# Peltier.net
KiCad netlist of a schematic drawn in Altium Designer
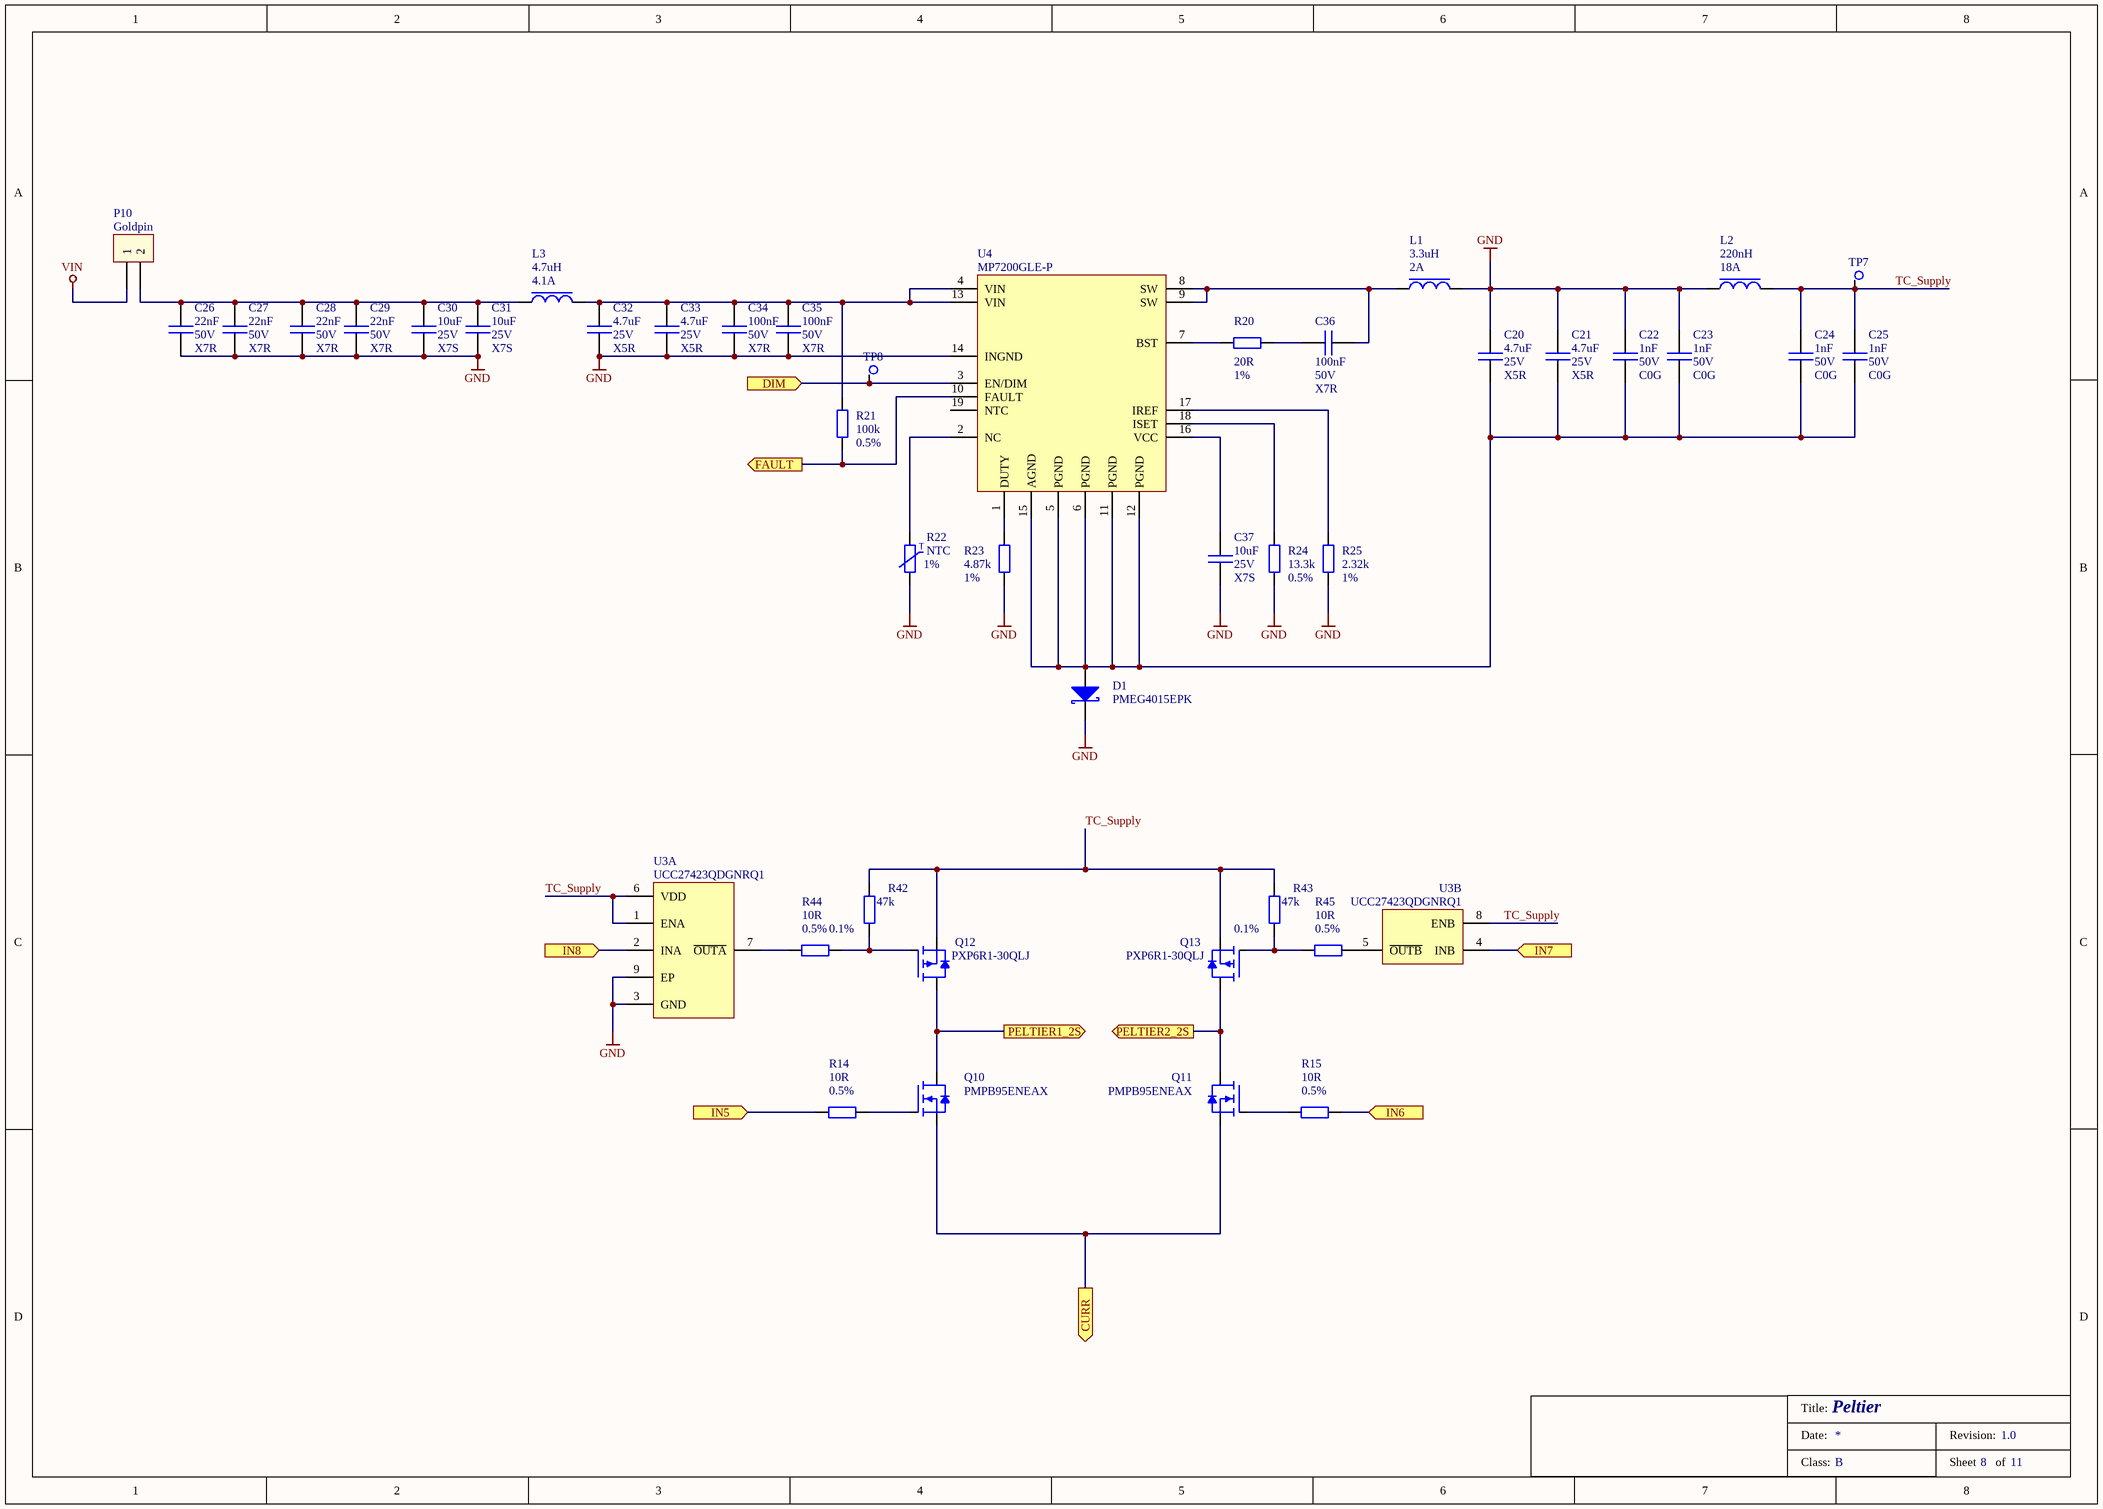
[diagram p0: Peltier.SchDoc]

(export (version "E")
  (design (tool "Eeschema 10.0.6"))
  (components
    (comp (ref "C20")
      (value "4.7uF")
      (footprint "C_0603")
      (description "Capacitor")
      (fields
        (field (name "VOLTAGE") "25V")
        (field (name "DIELECTRIC") "X5R")
        (field (name "PART NUMBER") "C_4.7uF_25V_0603")
        (field (name "MANUFACTURER") "TDK")
      )
      (libsource (lib "ProgresjaSpace") (part "C"))
    )
    (comp (ref "C21")
      (value "4.7uF")
      (footprint "C_0603")
      (description "Capacitor")
      (fields
        (field (name "VOLTAGE") "25V")
        (field (name "DIELECTRIC") "X5R")
        (field (name "PART NUMBER") "C_4.7uF_25V_0603")
        (field (name "MANUFACTURER") "TDK")
      )
      (libsource (lib "ProgresjaSpace") (part "C"))
    )
    (comp (ref "C22")
      (value "1nF")
      (footprint "C_0603")
      (description "Capacitor")
      (fields
        (field (name "VOLTAGE") "50V")
        (field (name "DIELECTRIC") "C0G")
        (field (name "PART NUMBER") "C_1nF_50V_0603")
        (field (name "MANUFACTURER") "Kemet")
      )
      (libsource (lib "ProgresjaSpace") (part "C"))
    )
    (comp (ref "C23")
      (value "1nF")
      (footprint "C_0603")
      (description "Capacitor")
      (fields
        (field (name "VOLTAGE") "50V")
        (field (name "DIELECTRIC") "C0G")
        (field (name "PART NUMBER") "C_1nF_50V_0603")
        (field (name "MANUFACTURER") "Kemet")
      )
      (libsource (lib "ProgresjaSpace") (part "C"))
    )
    (comp (ref "C24")
      (value "1nF")
      (footprint "C_0603")
      (description "Capacitor")
      (fields
        (field (name "VOLTAGE") "50V")
        (field (name "DIELECTRIC") "C0G")
        (field (name "PART NUMBER") "C_1nF_50V_0603")
        (field (name "MANUFACTURER") "Kemet")
      )
      (libsource (lib "ProgresjaSpace") (part "C"))
    )
    (comp (ref "C25")
      (value "1nF")
      (footprint "C_0603")
      (description "Capacitor")
      (fields
        (field (name "VOLTAGE") "50V")
        (field (name "DIELECTRIC") "C0G")
        (field (name "PART NUMBER") "C_1nF_50V_0603")
        (field (name "MANUFACTURER") "Kemet")
      )
      (libsource (lib "ProgresjaSpace") (part "C"))
    )
    (comp (ref "C26")
      (value "22nF")
      (footprint "C_0603")
      (description "Capacitor")
      (fields
        (field (name "VOLTAGE") "50V")
        (field (name "DIELECTRIC") "X7R")
        (field (name "PART NUMBER") "C_22nF_50V_0603")
        (field (name "MANUFACTURER") "Kemet")
      )
      (libsource (lib "ProgresjaSpace") (part "C"))
    )
    (comp (ref "C27")
      (value "22nF")
      (footprint "C_0603")
      (description "Capacitor")
      (fields
        (field (name "VOLTAGE") "50V")
        (field (name "DIELECTRIC") "X7R")
        (field (name "PART NUMBER") "C_22nF_50V_0603")
        (field (name "MANUFACTURER") "Kemet")
      )
      (libsource (lib "ProgresjaSpace") (part "C"))
    )
    (comp (ref "C28")
      (value "22nF")
      (footprint "C_0603")
      (description "Capacitor")
      (fields
        (field (name "VOLTAGE") "50V")
        (field (name "DIELECTRIC") "X7R")
        (field (name "PART NUMBER") "C_22nF_50V_0603")
        (field (name "MANUFACTURER") "Kemet")
      )
      (libsource (lib "ProgresjaSpace") (part "C"))
    )
    (comp (ref "C29")
      (value "22nF")
      (footprint "C_0603")
      (description "Capacitor")
      (fields
        (field (name "VOLTAGE") "50V")
        (field (name "DIELECTRIC") "X7R")
        (field (name "PART NUMBER") "C_22nF_50V_0603")
        (field (name "MANUFACTURER") "Kemet")
      )
      (libsource (lib "ProgresjaSpace") (part "C"))
    )
    (comp (ref "C30")
      (value "10uF")
      (footprint "C_0805")
      (description "Capacitor")
      (fields
        (field (name "VOLTAGE") "25V")
        (field (name "DIELECTRIC") "X7S")
        (field (name "PART NUMBER") "C_10uF_25V_0805")
        (field (name "MANUFACTURER") "TDK")
      )
      (libsource (lib "ProgresjaSpace") (part "C"))
    )
    (comp (ref "C31")
      (value "10uF")
      (footprint "C_0805")
      (description "Capacitor")
      (fields
        (field (name "VOLTAGE") "25V")
        (field (name "DIELECTRIC") "X7S")
        (field (name "PART NUMBER") "C_10uF_25V_0805")
        (field (name "MANUFACTURER") "TDK")
      )
      (libsource (lib "ProgresjaSpace") (part "C"))
    )
    (comp (ref "C32")
      (value "4.7uF")
      (footprint "C_0603")
      (description "Capacitor")
      (fields
        (field (name "VOLTAGE") "25V")
        (field (name "DIELECTRIC") "X5R")
        (field (name "PART NUMBER") "C_4.7uF_25V_0603")
        (field (name "MANUFACTURER") "TDK")
      )
      (libsource (lib "ProgresjaSpace") (part "C"))
    )
    (comp (ref "C33")
      (value "4.7uF")
      (footprint "C_0603")
      (description "Capacitor")
      (fields
        (field (name "VOLTAGE") "25V")
        (field (name "DIELECTRIC") "X5R")
        (field (name "PART NUMBER") "C_4.7uF_25V_0603")
        (field (name "MANUFACTURER") "TDK")
      )
      (libsource (lib "ProgresjaSpace") (part "C"))
    )
    (comp (ref "C34")
      (value "100nF")
      (footprint "C_0603")
      (description "Capacitor")
      (fields
        (field (name "VOLTAGE") "50V")
        (field (name "DIELECTRIC") "X7R")
        (field (name "PART NUMBER") "C_100nF_50V_0603")
        (field (name "MANUFACTURER") "Kemet")
      )
      (libsource (lib "ProgresjaSpace") (part "C"))
    )
    (comp (ref "C35")
      (value "100nF")
      (footprint "C_0603")
      (description "Capacitor")
      (fields
        (field (name "VOLTAGE") "50V")
        (field (name "DIELECTRIC") "X7R")
        (field (name "PART NUMBER") "C_100nF_50V_0603")
        (field (name "MANUFACTURER") "Kemet")
      )
      (libsource (lib "ProgresjaSpace") (part "C"))
    )
    (comp (ref "C36")
      (value "100nF")
      (footprint "C_0603")
      (description "Capacitor")
      (fields
        (field (name "VOLTAGE") "50V")
        (field (name "DIELECTRIC") "X7R")
        (field (name "PART NUMBER") "C_100nF_50V_0603")
        (field (name "MANUFACTURER") "Kemet")
      )
      (libsource (lib "ProgresjaSpace") (part "C"))
    )
    (comp (ref "C37")
      (value "10uF")
      (footprint "C_0805")
      (description "Capacitor")
      (fields
        (field (name "VOLTAGE") "25V")
        (field (name "DIELECTRIC") "X7S")
        (field (name "PART NUMBER") "C_10uF_25V_0805")
        (field (name "MANUFACTURER") "TDK")
      )
      (libsource (lib "ProgresjaSpace") (part "C"))
    )
    (comp (ref "D1")
      (value "PMEG4015EPK")
      (footprint "D_SOD_1608")
      (description "40 V, 1.5 A low VF MEGA Schottky barrier rectifier")
      (fields (field (name "MANUFACTURER") "Nexperia") (field (name "Comment") "D_SHOTTKY"))
      (libsource (lib "ProgresjaSpace") (part "D_SHOTTKY"))
    )
    (comp (ref "L1")
      (value "3.3uH")
      (footprint "L_1008_05")
      (description "Shielded, soft-termination")
      (fields
        (field (name "MAX CURRENT") "2A")
        (field (name "PART NUMBER") "TFM252012ALVA3R3MTAA")
        (field (name "MANUFACTURER") "TDK")
      )
      (libsource (lib "ProgresjaSpace") (part "L_Core"))
    )
    (comp (ref "L2")
      (value "220nH")
      (footprint "L_2020")
      (description "Shielded Inductors, High Temperature")
      (fields
        (field (name "MAX CURRENT") "18A")
        (field (name "PART NUMBER") "IHLP2020CZERR22M8A")
        (field (name "MANUFACTURER") "Vishay")
      )
      (libsource (lib "ProgresjaSpace") (part "L_Core"))
    )
    (comp (ref "L3")
      (value "4.7uH")
      (footprint "L_2020")
      (description "Shielded automotive Inductors, High Temperature")
      (fields
        (field (name "MAX CURRENT") "4.1A")
        (field (name "PART NUMBER") "IHLP2020CZER4R7M5A")
        (field (name "MANUFACTURER") "Vishay")
      )
      (libsource (lib "ProgresjaSpace") (part "L_Core"))
    )
    (comp (ref "P10")
      (value "P_Header_2")
      (footprint "GOLDPIN_2")
      (description "Goldpin")
      (fields
        (field (name "DESC") "Goldpin")
        (field (name "PART NUMBER") "77311-818-02LF")
        (field (name "MANUFACTURER") "AMPHENOL")
      )
      (libsource (lib "ProgresjaSpace") (part "P_Header_2"))
    )
    (comp (ref "Q10")
      (value "PMPB95ENEAX")
      (footprint "UDFN_6_3123")
      (description "Single N-channel Trench MOSFET")
      (fields (field (name "MANUFACTURER") "NEXPERIA") (field (name "Comment") "Q_NMOSFET"))
      (libsource (lib "ProgresjaSpace") (part "Q_NMOSFET"))
    )
    (comp (ref "Q11")
      (value "PMPB95ENEAX")
      (footprint "UDFN_6_3123")
      (description "Single N-channel Trench MOSFET")
      (fields (field (name "MANUFACTURER") "NEXPERIA") (field (name "Comment") "Q_NMOSFET"))
      (libsource (lib "ProgresjaSpace") (part "Q_NMOSFET"))
    )
    (comp (ref "Q12")
      (value "PXP6R1-30QLJ")
      (footprint "WDFN_8")
      (description "Low Vgs Single P-Channel")
      (fields (field (name "MANUFACTURER") "NEXPERIA") (field (name "Comment") "Q_PMOSFET"))
      (libsource (lib "ProgresjaSpace") (part "Q_PMOSFET"))
    )
    (comp (ref "Q13")
      (value "PXP6R1-30QLJ")
      (footprint "WDFN_8")
      (description "Low Vgs Single P-Channel")
      (fields (field (name "MANUFACTURER") "NEXPERIA") (field (name "Comment") "Q_PMOSFET"))
      (libsource (lib "ProgresjaSpace") (part "Q_PMOSFET"))
    )
    (comp (ref "R14")
      (value "10R")
      (footprint "R_0603")
      (fields
        (field (name "TOLERANCE") "0.5%")
        (field (name "PART NUMBER") "R_10R_75V_0603")
        (field (name "VOLTAGE") "75V")
        (field (name "MANUFACTURER") "Vishay")
      )
      (libsource (lib "ProgresjaSpace") (part "R"))
    )
    (comp (ref "R15")
      (value "10R")
      (footprint "R_0603")
      (fields
        (field (name "TOLERANCE") "0.5%")
        (field (name "PART NUMBER") "R_10R_75V_0603")
        (field (name "VOLTAGE") "75V")
        (field (name "MANUFACTURER") "Vishay")
      )
      (libsource (lib "ProgresjaSpace") (part "R"))
    )
    (comp (ref "R20")
      (value "20R")
      (footprint "R_0603")
      (fields
        (field (name "TOLERANCE") "1%")
        (field (name "PART NUMBER") "R_20R_75V_0603")
        (field (name "VOLTAGE") "75V")
        (field (name "MANUFACTURER") "Panasonic")
      )
      (libsource (lib "ProgresjaSpace") (part "R"))
    )
    (comp (ref "R21")
      (value "100k")
      (footprint "R_0402")
      (fields
        (field (name "TOLERANCE") "0.5%")
        (field (name "PART NUMBER") "R_100k_50V_0402")
        (field (name "VOLTAGE") "50V")
        (field (name "MANUFACTURER") "Vishay")
      )
      (libsource (lib "") (part "R_1"))
    )
    (comp (ref "R22")
      (value "R_B572xxV5")
      (footprint "R_0402")
      (description "NTC")
      (fields
        (field (name "DESC") "NTC")
        (field (name "TOLERANCE") "1%")
        (field (name "PART NUMBER") "B57232V5103F360")
        (field (name "MANUFACTURER") "TDK")
      )
      (libsource (lib "ProgresjaSpace") (part "R_B572xxV5"))
    )
    (comp (ref "R23")
      (value "4.87k")
      (footprint "R_0402")
      (fields
        (field (name "TOLERANCE") "1%")
        (field (name "PART NUMBER") "R_4.87k_50V_0402")
        (field (name "VOLTAGE") "50V")
        (field (name "MANUFACTURER") "Panasonic")
      )
      (libsource (lib "") (part "R_1"))
    )
    (comp (ref "R24")
      (value "13.3k")
      (footprint "R_0402")
      (fields
        (field (name "TOLERANCE") "0.5%")
        (field (name "PART NUMBER") "R_13.3k_50V_0402")
        (field (name "VOLTAGE") "50V")
        (field (name "MANUFACTURER") "Panasonic")
      )
      (libsource (lib "") (part "R_1"))
    )
    (comp (ref "R25")
      (value "2.32k")
      (footprint "R_0402")
      (fields
        (field (name "TOLERANCE") "1%")
        (field (name "PART NUMBER") "R_2.32k_50V_0402")
        (field (name "VOLTAGE") "50V")
        (field (name "MANUFACTURER") "Panasonic")
      )
      (libsource (lib "") (part "R_1"))
    )
    (comp (ref "R42")
      (value "47k")
      (footprint "R_0402")
      (fields
        (field (name "TOLERANCE") "0.1%")
        (field (name "PART NUMBER") "R_47k_50V_0402")
        (field (name "VOLTAGE") "50V")
        (field (name "MANUFACTURER") "Vishay")
      )
      (libsource (lib "") (part "R_2"))
    )
    (comp (ref "R43")
      (value "47k")
      (footprint "R_0402")
      (fields
        (field (name "TOLERANCE") "0.1%")
        (field (name "PART NUMBER") "R_47k_50V_0402")
        (field (name "VOLTAGE") "50V")
        (field (name "MANUFACTURER") "Vishay")
      )
      (libsource (lib "") (part "R_2"))
    )
    (comp (ref "R44")
      (value "10R")
      (footprint "R_0603")
      (fields
        (field (name "TOLERANCE") "0.5%")
        (field (name "PART NUMBER") "R_10R_75V_0603")
        (field (name "VOLTAGE") "75V")
        (field (name "MANUFACTURER") "Vishay")
      )
      (libsource (lib "ProgresjaSpace") (part "R"))
    )
    (comp (ref "R45")
      (value "10R")
      (footprint "R_0603")
      (fields
        (field (name "TOLERANCE") "0.5%")
        (field (name "PART NUMBER") "R_10R_75V_0603")
        (field (name "VOLTAGE") "75V")
        (field (name "MANUFACTURER") "Vishay")
      )
      (libsource (lib "ProgresjaSpace") (part "R"))
    )
    (comp (ref "TP7")
      (value "TP_TestPoint")
      (footprint "TP_01")
      (fields (field (name "PART NUMBER") "TestPoint1") (field (name "MANUFACTURER") "Progresja Space"))
      (libsource (lib "ProgresjaSpace") (part "TP_TestPoint"))
    )
    (comp (ref "TP8")
      (value "TP_TestPoint")
      (footprint "TP_01")
      (fields (field (name "PART NUMBER") "TestPoint1") (field (name "MANUFACTURER") "Progresja Space"))
      (libsource (lib "ProgresjaSpace") (part "TP_TestPoint"))
    )
    (comp (ref "U3")
      (value "UCC27423QDGNRQ1")
      (footprint "MSOP_8")
      (description "Dual 4-A High-Speed Low-Side MOSFET Drivers With Enable")
      (fields (field (name "PART NUMBER") "UCC27423") (field (name "MANUFACTURER") "TI"))
      (libsource (lib "") (part "IC_UCC27423_Q1_1"))
    )
    (comp (ref "U4")
      (value "IC_MP7200")
      (footprint "QFN_19")
      (description "Continous current Buck-Boost DC-DC Converter")
      (fields
        (field (name "=VALUE") "MP7200GLE-P")
        (field (name "PART NUMBER") "MP7200GLE-P")
        (field (name "MANUFACTURER") "MPS")
      )
      (libsource (lib "ProgresjaSpace") (part "IC_MP7200"))
    )
  )
  (nets
    (net (code "1") (name "/CURR") (class "Default")
      (node (ref "Q10") (pin "2") (pinfunction "S_2") (pintype "passive"))
      (node (ref "Q11") (pin "2") (pinfunction "S_2") (pintype "passive"))
    )
    (net (code "2") (name "/DIM") (class "Default")
      (node (ref "TP8") (pin "1") (pinfunction "1_1") (pintype "passive"))
      (node (ref "U4") (pin "3") (pinfunction "EN/DIM_3") (pintype "passive"))
    )
    (net (code "3") (name "/FAULT") (class "Default")
      (node (ref "R21") (pin "2") (pinfunction "2_2") (pintype "passive"))
      (node (ref "U4") (pin "10") (pinfunction "FAULT_10") (pintype "passive"))
    )
    (net (code "4") (name "/IN5") (class "Default")
      (node (ref "R14") (pin "1") (pinfunction "1_1") (pintype "passive"))
    )
    (net (code "5") (name "/IN6") (class "Default")
      (node (ref "R15") (pin "2") (pinfunction "2_2") (pintype "passive"))
    )
    (net (code "6") (name "/IN7") (class "Default")
      (node (ref "U3") (pin "4") (pinfunction "INB_4") (pintype "passive"))
    )
    (net (code "7") (name "/IN8") (class "Default")
      (node (ref "U3") (pin "2") (pinfunction "INA_2") (pintype "passive"))
    )
    (net (code "8") (name "/PELTIER1_2S") (class "Default")
      (node (ref "Q10") (pin "3") (pinfunction "D_3") (pintype "passive"))
      (node (ref "Q12") (pin "3") (pinfunction "D_3") (pintype "passive"))
    )
    (net (code "9") (name "/PELTIER2_2S") (class "Default")
      (node (ref "Q11") (pin "3") (pinfunction "D_3") (pintype "passive"))
      (node (ref "Q13") (pin "3") (pinfunction "D_3") (pintype "passive"))
    )
    (net (code "10") (name "/TC_Supply") (class "Default")
      (node (ref "C24") (pin "1") (pinfunction "1_1") (pintype "passive"))
      (node (ref "C25") (pin "1") (pinfunction "1_1") (pintype "passive"))
      (node (ref "L2") (pin "2") (pinfunction "2_2") (pintype "passive"))
      (node (ref "Q12") (pin "2") (pinfunction "S_2") (pintype "passive"))
      (node (ref "Q13") (pin "2") (pinfunction "S_2") (pintype "passive"))
      (node (ref "R42") (pin "1") (pinfunction "1_1") (pintype "passive"))
      (node (ref "R43") (pin "1") (pinfunction "1_1") (pintype "passive"))
      (node (ref "TP7") (pin "1") (pinfunction "1_1") (pintype "passive"))
      (node (ref "U3") (pin "1") (pinfunction "ENA_1") (pintype "passive"))
      (node (ref "U3") (pin "6") (pinfunction "VDD_6") (pintype "passive"))
      (node (ref "U3") (pin "8") (pinfunction "ENB_8") (pintype "passive"))
    )
    (net (code "11") (name "GND") (class "Default")
      (node (ref "C20") (pin "1") (pinfunction "1_1") (pintype "passive"))
      (node (ref "C21") (pin "1") (pinfunction "1_1") (pintype "passive"))
      (node (ref "C22") (pin "1") (pinfunction "1_1") (pintype "passive"))
      (node (ref "C23") (pin "1") (pinfunction "1_1") (pintype "passive"))
      (node (ref "C26") (pin "2") (pinfunction "2_2") (pintype "passive"))
      (node (ref "C27") (pin "2") (pinfunction "2_2") (pintype "passive"))
      (node (ref "C28") (pin "2") (pinfunction "2_2") (pintype "passive"))
      (node (ref "C29") (pin "2") (pinfunction "2_2") (pintype "passive"))
      (node (ref "C30") (pin "2") (pinfunction "2_2") (pintype "passive"))
      (node (ref "C31") (pin "2") (pinfunction "2_2") (pintype "passive"))
      (node (ref "C32") (pin "2") (pinfunction "2_2") (pintype "passive"))
      (node (ref "C33") (pin "2") (pinfunction "2_2") (pintype "passive"))
      (node (ref "C34") (pin "2") (pinfunction "2_2") (pintype "passive"))
      (node (ref "C35") (pin "2") (pinfunction "2_2") (pintype "passive"))
      (node (ref "C37") (pin "2") (pinfunction "2_2") (pintype "passive"))
      (node (ref "D1") (pin "2") (pinfunction "K_2") (pintype "passive"))
      (node (ref "L1") (pin "2") (pinfunction "2_2") (pintype "passive"))
      (node (ref "L2") (pin "1") (pinfunction "1_1") (pintype "passive"))
      (node (ref "R22") (pin "2") (pinfunction "2_2") (pintype "passive"))
      (node (ref "R23") (pin "2") (pinfunction "2_2") (pintype "passive"))
      (node (ref "R24") (pin "2") (pinfunction "2_2") (pintype "passive"))
      (node (ref "R25") (pin "2") (pinfunction "2_2") (pintype "passive"))
      (node (ref "U3") (pin "3") (pinfunction "GND_3") (pintype "passive"))
      (node (ref "U3") (pin "9") (pinfunction "EP_9") (pintype "passive"))
      (node (ref "U4") (pin "14") (pinfunction "INGND_14") (pintype "passive"))
    )
    (net (code "12") (name "Net-(C26-Pad1)") (class "Default")
      (node (ref "C26") (pin "1") (pinfunction "1_1") (pintype "passive"))
      (node (ref "C27") (pin "1") (pinfunction "1_1") (pintype "passive"))
      (node (ref "C28") (pin "1") (pinfunction "1_1") (pintype "passive"))
      (node (ref "C29") (pin "1") (pinfunction "1_1") (pintype "passive"))
      (node (ref "C30") (pin "1") (pinfunction "1_1") (pintype "passive"))
      (node (ref "C31") (pin "1") (pinfunction "1_1") (pintype "passive"))
      (node (ref "L3") (pin "1") (pinfunction "1_1") (pintype "passive"))
      (node (ref "P10") (pin "2") (pinfunction "2_2") (pintype "passive"))
    )
    (net (code "13") (name "Net-(C32-Pad1)") (class "Default")
      (node (ref "C32") (pin "1") (pinfunction "1_1") (pintype "passive"))
      (node (ref "C33") (pin "1") (pinfunction "1_1") (pintype "passive"))
      (node (ref "C34") (pin "1") (pinfunction "1_1") (pintype "passive"))
      (node (ref "C35") (pin "1") (pinfunction "1_1") (pintype "passive"))
      (node (ref "L3") (pin "2") (pinfunction "2_2") (pintype "passive"))
      (node (ref "R21") (pin "1") (pinfunction "1_1") (pintype "passive"))
      (node (ref "U4") (pin "13") (pinfunction "VIN_13") (pintype "passive"))
      (node (ref "U4") (pin "4") (pinfunction "VIN_4") (pintype "passive"))
    )
    (net (code "14") (name "Net-(C36-Pad1)") (class "Default")
      (node (ref "C36") (pin "1") (pinfunction "1_1") (pintype "passive"))
      (node (ref "R20") (pin "2") (pinfunction "2_2") (pintype "passive"))
    )
    (net (code "15") (name "Net-(C36-Pad2)") (class "Default")
      (node (ref "C36") (pin "2") (pinfunction "2_2") (pintype "passive"))
      (node (ref "L1") (pin "1") (pinfunction "1_1") (pintype "passive"))
      (node (ref "U4") (pin "8") (pinfunction "SW_8") (pintype "passive"))
      (node (ref "U4") (pin "9") (pinfunction "SW_9") (pintype "passive"))
    )
    (net (code "16") (name "Net-(D1-A)") (class "Default")
      (node (ref "C20") (pin "2") (pinfunction "2_2") (pintype "passive"))
      (node (ref "C21") (pin "2") (pinfunction "2_2") (pintype "passive"))
      (node (ref "C22") (pin "2") (pinfunction "2_2") (pintype "passive"))
      (node (ref "C23") (pin "2") (pinfunction "2_2") (pintype "passive"))
      (node (ref "C24") (pin "2") (pinfunction "2_2") (pintype "passive"))
      (node (ref "C25") (pin "2") (pinfunction "2_2") (pintype "passive"))
      (node (ref "D1") (pin "1") (pinfunction "A_1") (pintype "passive"))
      (node (ref "U4") (pin "11") (pinfunction "PGND_11") (pintype "passive"))
      (node (ref "U4") (pin "12") (pinfunction "PGND_12") (pintype "passive"))
      (node (ref "U4") (pin "15") (pinfunction "AGND_15") (pintype "passive"))
      (node (ref "U4") (pin "5") (pinfunction "PGND_5") (pintype "passive"))
      (node (ref "U4") (pin "6") (pinfunction "PGND_6") (pintype "passive"))
    )
    (net (code "17") (name "Net-(Q10-G)") (class "Default")
      (node (ref "Q10") (pin "1") (pinfunction "G_1") (pintype "passive"))
      (node (ref "R14") (pin "2") (pinfunction "2_2") (pintype "passive"))
    )
    (net (code "18") (name "Net-(Q11-G)") (class "Default")
      (node (ref "Q11") (pin "1") (pinfunction "G_1") (pintype "passive"))
      (node (ref "R15") (pin "1") (pinfunction "1_1") (pintype "passive"))
    )
    (net (code "19") (name "Net-(Q12-G)") (class "Default")
      (node (ref "Q12") (pin "1") (pinfunction "G_1") (pintype "passive"))
      (node (ref "R42") (pin "2") (pinfunction "2_2") (pintype "passive"))
      (node (ref "R44") (pin "2") (pinfunction "2_2") (pintype "passive"))
    )
    (net (code "20") (name "Net-(Q13-G)") (class "Default")
      (node (ref "Q13") (pin "1") (pinfunction "G_1") (pintype "passive"))
      (node (ref "R43") (pin "2") (pinfunction "2_2") (pintype "passive"))
      (node (ref "R45") (pin "1") (pinfunction "1_1") (pintype "passive"))
    )
    (net (code "21") (name "Net-(U3A-~{OUTA})") (class "Default")
      (node (ref "R44") (pin "1") (pinfunction "1_1") (pintype "passive"))
      (node (ref "U3") (pin "7") (pinfunction "~{OUTA}_7") (pintype "passive"))
    )
    (net (code "22") (name "Net-(U3B-~{OUTB})") (class "Default")
      (node (ref "R45") (pin "2") (pinfunction "2_2") (pintype "passive"))
      (node (ref "U3") (pin "5") (pinfunction "~{OUTB}_5") (pintype "passive"))
    )
    (net (code "23") (name "Net-(U4-BST)") (class "Default")
      (node (ref "R20") (pin "1") (pinfunction "1_1") (pintype "passive"))
      (node (ref "U4") (pin "7") (pinfunction "BST_7") (pintype "passive"))
    )
    (net (code "24") (name "Net-(U4-DUTY)") (class "Default")
      (node (ref "R23") (pin "1") (pinfunction "1_1") (pintype "passive"))
      (node (ref "U4") (pin "1") (pinfunction "DUTY_1") (pintype "passive"))
    )
    (net (code "25") (name "Net-(U4-IREF)") (class "Default")
      (node (ref "R25") (pin "1") (pinfunction "1_1") (pintype "passive"))
      (node (ref "U4") (pin "17") (pinfunction "IREF_17") (pintype "passive"))
    )
    (net (code "26") (name "Net-(U4-ISET)") (class "Default")
      (node (ref "R24") (pin "1") (pinfunction "1_1") (pintype "passive"))
      (node (ref "U4") (pin "18") (pinfunction "ISET_18") (pintype "passive"))
    )
    (net (code "27") (name "Net-(U4-NC)") (class "Default")
      (node (ref "R22") (pin "1") (pinfunction "1_1") (pintype "passive"))
      (node (ref "U4") (pin "2") (pinfunction "NC_2") (pintype "passive"))
    )
    (net (code "28") (name "Net-(U4-VCC)") (class "Default")
      (node (ref "C37") (pin "1") (pinfunction "1_1") (pintype "passive"))
      (node (ref "U4") (pin "16") (pinfunction "VCC_16") (pintype "passive"))
    )
    (net (code "29") (name "VIN") (class "Default")
      (node (ref "P10") (pin "1") (pinfunction "1_1") (pintype "passive"))
    )
    (net (code "30") (name "unconnected-(U4-NTC-Pad19)") (class "Default")
      (node (ref "U4") (pin "19") (pinfunction "NTC_19") (pintype "passive"))
    )
  )
)
